# 09_SARADC_OTP.net
KiCad netlist of a schematic drawn in Altium Designer
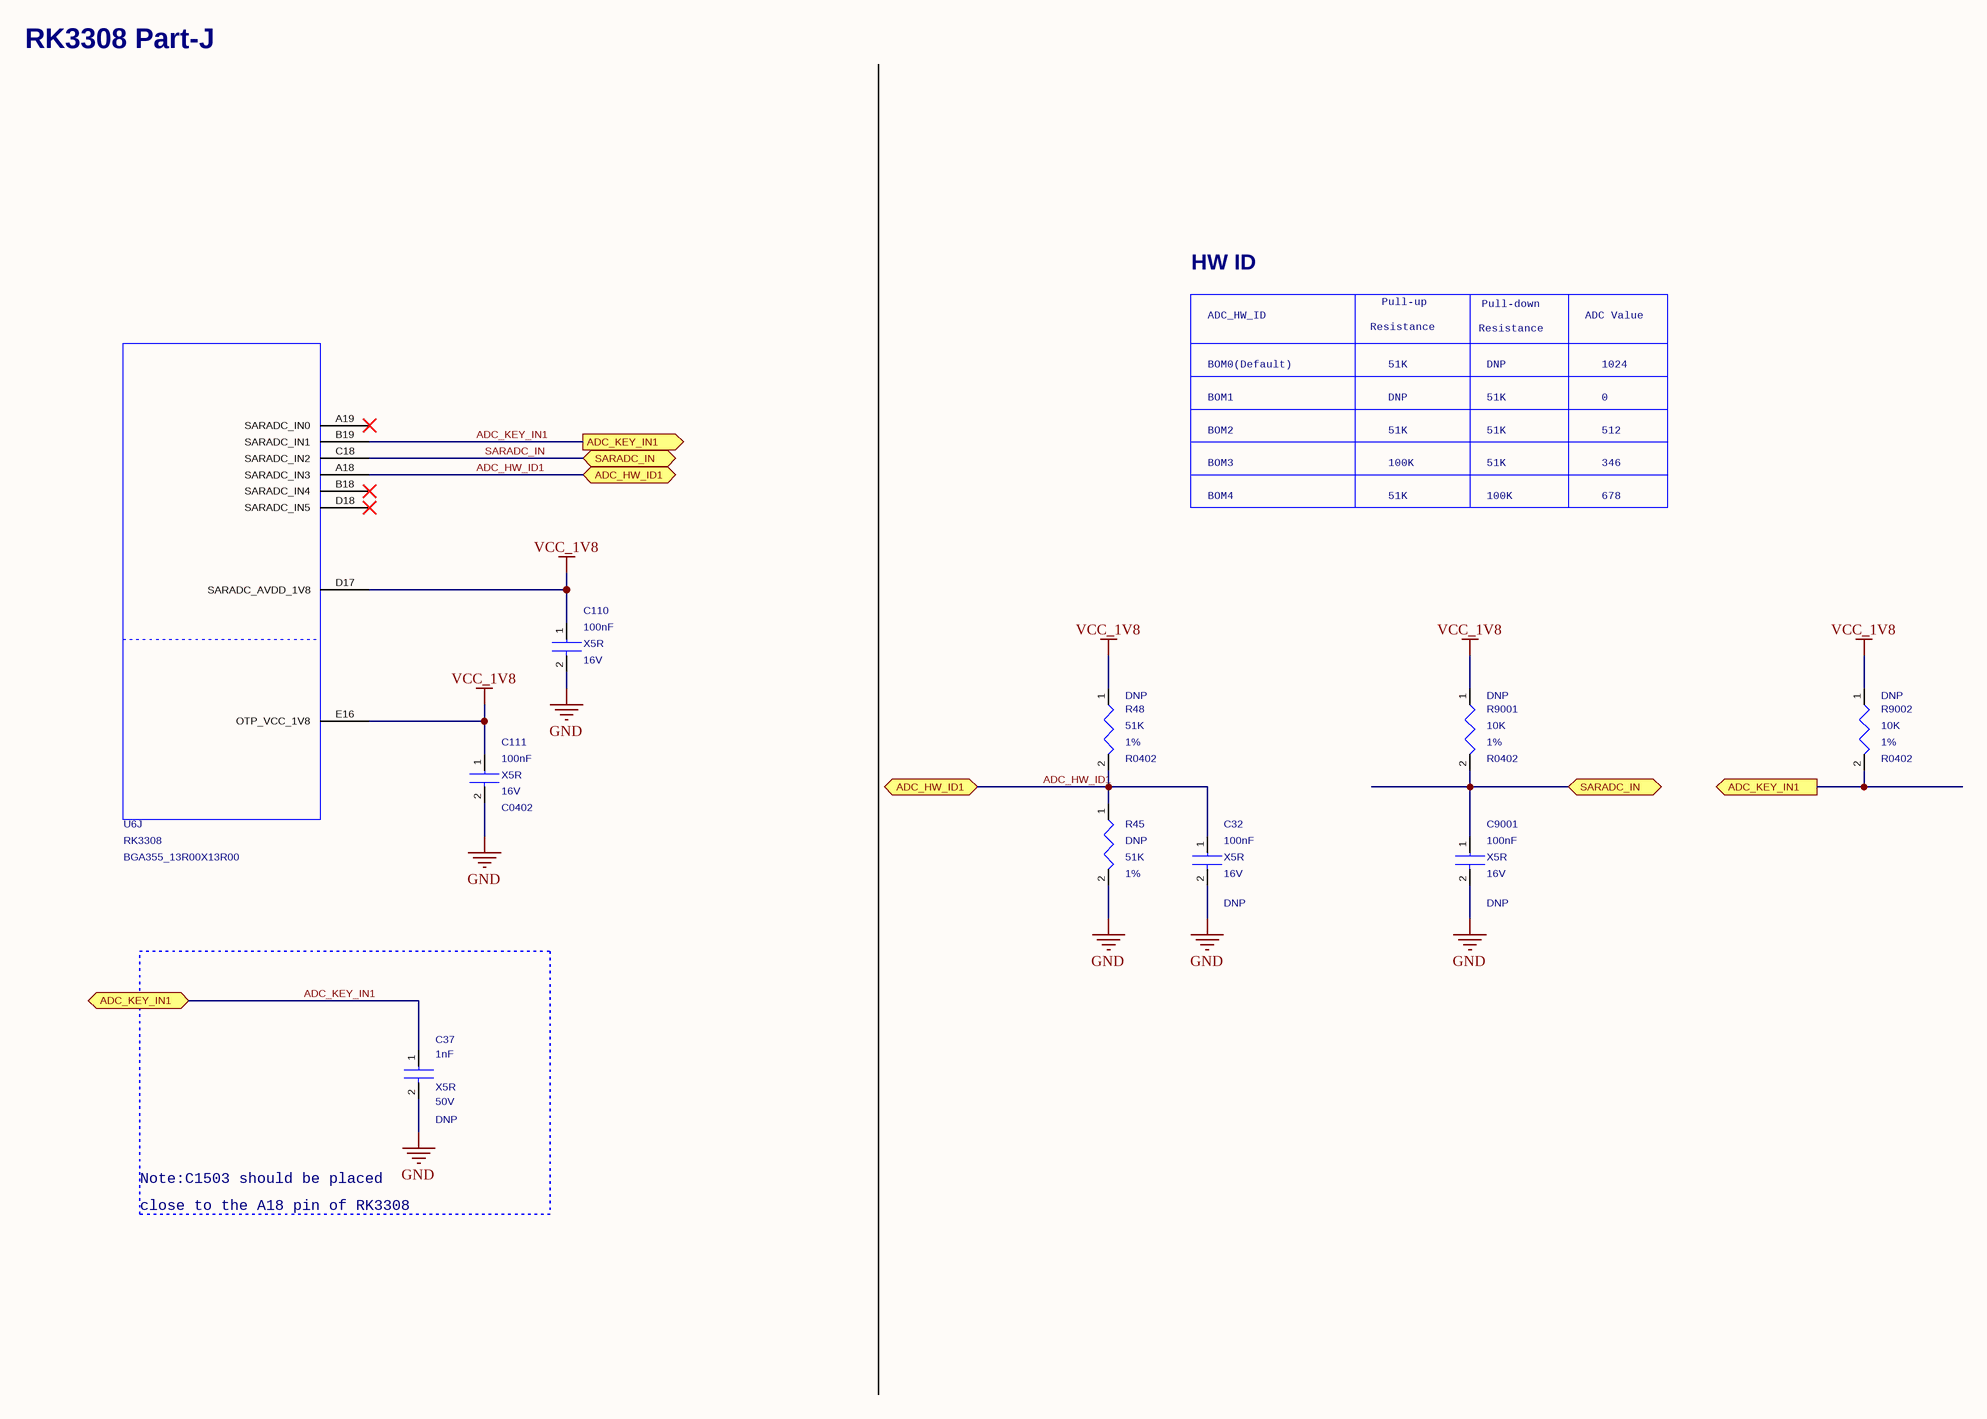
[diagram p0: 09_SARADC_OTP.SchDoc]

(export (version "E")
  (design (tool "Eeschema 10.0.6"))
  (components
    (comp (ref "C32")
      (value "100nF")
      (footprint "C0402")
      (description "cap,100.00nF,+/-10%,16V,X5R,C0402")
      (fields
        (field (name "DIELECTRIC") "X5R")
        (field (name "MANUFACTURER") "TDK")
        (field (name "TOLERANCE") "10%")
        (field (name "VOLTAGE") "16V")
        (field (name "OPTION") "DNP")
        (field (name "CREATED_BY") "JJJ")
      )
      (libsource (lib "*") (part "CAP_NP_2"))
    )
    (comp (ref "C37")
      (value "1nF")
      (footprint "C0402")
      (description "cap,1.00nF,+/-10%,50V,X5R,C0402")
      (fields
        (field (name "DIELECTRIC") "X5R")
        (field (name "VOLTAGE") "50V")
        (field (name "TOLERANCE") "10%")
        (field (name "MANUFACTURER") "TDK")
        (field (name "OPTION") "DNP")
        (field (name "CREATED_BY") "JJJ")
      )
      (libsource (lib "*") (part "CAP_NP_2"))
    )
    (comp (ref "C110")
      (value "100nF")
      (footprint "C0402")
      (description "cap,100.00nF,+/-10%,16V,X5R,C0402")
      (fields
        (field (name "VOLTAGE") "16V")
        (field (name "TOLERANCE") "10%")
        (field (name "MANUFACTURER") "TDK")
        (field (name "DIELECTRIC") "X5R")
        (field (name "CREATED_BY") "JJJ")
      )
      (libsource (lib "*") (part "CAP_NP_2"))
    )
    (comp (ref "C111")
      (value "100nF")
      (footprint "C0402")
      (description "cap,100.00nF,+/-10%,16V,X5R,C0402")
      (fields
        (field (name "PCB DECAL") "C0402")
        (field (name "VOLTAGE") "16V")
        (field (name "TOLERANCE") "10%")
        (field (name "MANUFACTURER") "TDK")
        (field (name "DIELECTRIC") "X5R")
        (field (name "CREATED_BY") "JJJ")
      )
      (libsource (lib "*") (part "CAP_NP_2"))
    )
    (comp (ref "C9001")
      (value "100nF")
      (footprint "C0402")
      (description "cap,100.00nF,+/-10%,16V,X5R,C0402")
      (fields
        (field (name "DIELECTRIC") "X5R")
        (field (name "MANUFACTURER") "TDK")
        (field (name "TOLERANCE") "10%")
        (field (name "VOLTAGE") "16V")
        (field (name "OPTION") "DNP")
        (field (name "CREATED_BY") "JJJ")
      )
      (libsource (lib "*") (part "CAP_NP_2"))
    )
    (comp (ref "R45")
      (value "51K")
      (footprint "R0402")
      (description "?用厚膜电阻,51K,+/-1%,R0402,1/16W.")
      (fields
        (field (name "OPTION") "DNP")
        (field (name "MANUFACTURER") "YAGEO")
        (field (name "TOLERANCE") "1%")
        (field (name "Comment") "RESISTOR")
        (field (name "CREATED_BY") "YTL")
      )
      (libsource (lib "*") (part "RESISTOR"))
    )
    (comp (ref "R48")
      (value "51K")
      (footprint "R0402")
      (description "?用厚膜电阻,51K,+/-1%,R0402,1/16W.")
      (fields
        (field (name "MANUFACTURER") "YAGEO")
        (field (name "TOLERANCE") "1%")
        (field (name "PCB DECAL") "R0402")
        (field (name "OPTION") "DNP")
        (field (name "Comment") "RESISTOR")
        (field (name "CREATED_BY") "YTL")
      )
      (libsource (lib "*") (part "RESISTOR"))
    )
    (comp (ref "R9001")
      (value "10K")
      (footprint "R0402")
      (description "?用厚膜电阻,10K,+/-1%,R0402,1/16W.")
      (fields
        (field (name "MANUFACTURER") "YAGEO")
        (field (name "TOLERANCE") "1%")
        (field (name "PCB DECAL") "R0402")
        (field (name "OPTION") "DNP")
        (field (name "Comment") "RESISTOR")
        (field (name "CREATED_BY") "YTL")
      )
      (libsource (lib "*") (part "RESISTOR"))
    )
    (comp (ref "R9002")
      (value "10K")
      (footprint "R0402")
      (description "?用厚膜电阻,10K,+/-1%,R0402,1/16W.")
      (fields
        (field (name "MANUFACTURER") "YAGEO")
        (field (name "TOLERANCE") "1%")
        (field (name "PCB DECAL") "R0402")
        (field (name "OPTION") "DNP")
        (field (name "Comment") "RESISTOR")
        (field (name "CREATED_BY") "YTL")
      )
      (libsource (lib "*") (part "RESISTOR"))
    )
    (comp (ref "U6")
      (value "RK3308")
      (footprint "BGA355_13R00X13R00")
      (fields (field (name "PCB DECAL") "BGA355_13R00X13R00") (field (name "MANUFACTURER") "ROCKCHIP"))
      (libsource (lib "*") (part "RK3308"))
    )
  )
  (nets
    (net (code "1") (name "/ADC_HW_ID1") (class "Default")
      (node (ref "C32") (pin "1") (pinfunction "1_1") (pintype "passive"))
      (node (ref "R45") (pin "1") (pinfunction "1_1") (pintype "passive"))
      (node (ref "R48") (pin "2") (pinfunction "2_2") (pintype "passive"))
      (node (ref "U6") (pin "A18") (pinfunction "SARADC_IN3_A18") (pintype "passive"))
    )
    (net (code "2") (name "/ADC_KEY_IN1") (class "Default")
      (node (ref "C37") (pin "1") (pinfunction "1_1") (pintype "passive"))
      (node (ref "R9002") (pin "2") (pinfunction "2_2") (pintype "passive"))
      (node (ref "U6") (pin "B19") (pinfunction "SARADC_IN1_B19") (pintype "passive"))
    )
    (net (code "3") (name "/SARADC_IN") (class "Default")
      (node (ref "C9001") (pin "1") (pinfunction "1_1") (pintype "passive"))
      (node (ref "R9001") (pin "2") (pinfunction "2_2") (pintype "passive"))
      (node (ref "U6") (pin "C18") (pinfunction "SARADC_IN2_C18") (pintype "passive"))
    )
    (net (code "4") (name "GND") (class "Default")
      (node (ref "C110") (pin "2") (pinfunction "2_2") (pintype "passive"))
      (node (ref "C111") (pin "2") (pinfunction "2_2") (pintype "passive"))
      (node (ref "C32") (pin "2") (pinfunction "2_2") (pintype "passive"))
      (node (ref "C37") (pin "2") (pinfunction "2_2") (pintype "passive"))
      (node (ref "C9001") (pin "2") (pinfunction "2_2") (pintype "passive"))
      (node (ref "R45") (pin "2") (pinfunction "2_2") (pintype "passive"))
    )
    (net (code "5") (name "VCC_1V8") (class "Default")
      (node (ref "C110") (pin "1") (pinfunction "1_1") (pintype "passive"))
      (node (ref "C111") (pin "1") (pinfunction "1_1") (pintype "passive"))
      (node (ref "R48") (pin "1") (pinfunction "1_1") (pintype "passive"))
      (node (ref "R9001") (pin "1") (pinfunction "1_1") (pintype "passive"))
      (node (ref "R9002") (pin "1") (pinfunction "1_1") (pintype "passive"))
      (node (ref "U6") (pin "D17") (pinfunction "SARADC_AVDD_1V8_D17") (pintype "passive"))
      (node (ref "U6") (pin "E16") (pinfunction "OTP_VCC_1V8_E16") (pintype "passive"))
    )
    (net (code "6") (name "unconnected-(U6J-SARADC_IN0-PadA19)") (class "Default")
      (node (ref "U6") (pin "A19") (pinfunction "SARADC_IN0_A19") (pintype "passive+no_connect"))
    )
    (net (code "7") (name "unconnected-(U6J-SARADC_IN4-PadB18)") (class "Default")
      (node (ref "U6") (pin "B18") (pinfunction "SARADC_IN4_B18") (pintype "passive+no_connect"))
    )
    (net (code "8") (name "unconnected-(U6J-SARADC_IN5-PadD18)") (class "Default")
      (node (ref "U6") (pin "D18") (pinfunction "SARADC_IN5_D18") (pintype "passive+no_connect"))
    )
  )
)
